# v1_0.net
KiCad netlist of a schematic drawn in Altium Designer
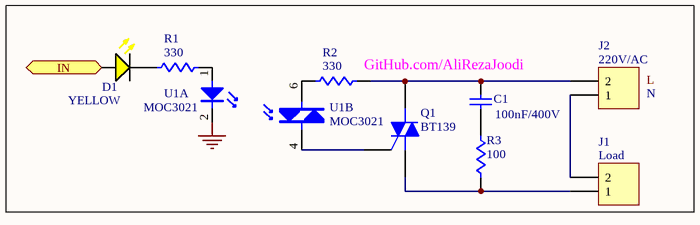
[diagram p0: v1.0.SchDoc]

(export (version "E")
  (design (tool "Eeschema 10.0.6"))
  (components
    (comp (ref "C1")
      (value "100nF/400V")
      (footprint "CAPR7.62-6.8x5")
      (description "Capacitor")
      (fields (field (name "MANUFACTURER") "Generic Components") (field (name "PUBLISHER") "Altium Limited"))
      (libsource (lib "Miscellaneous Devices") (part "Cap"))
    )
    (comp (ref "D1")
      (value "YELLOW")
      (footprint "LED_THD_5MM_YELLOW")
      (description "LED, Yellow")
      (fields (field (name "MANUFACTURER") "Generic Components") (field (name "PUBLISHER") "Altium Limited"))
      (libsource (lib "Display") (part "LED_YELLOW"))
    )
    (comp (ref "J1")
      (value "2PIN")
      (footprint "Fonics_2PIN_1")
      (description "Header, 2-Pin")
      (fields (field (name "PUBLISHER") "Altium Limited"))
      (libsource (lib "Miscellaneous Connectors") (part "Header 2"))
    )
    (comp (ref "J2")
      (value "2PIN")
      (footprint "Fonics_2PIN_1")
      (description "Header, 2-Pin")
      (fields (field (name "PUBLISHER") "Altium Limited"))
      (libsource (lib "Miscellaneous Connectors") (part "Header 2"))
    )
    (comp (ref "Q1")
      (value "BT139")
      (footprint "TO220V")
      (description "Silicon Bidirectional Triode Thyristor")
      (fields (field (name "MANUFACTURER") "Generic Components") (field (name "PUBLISHER") "Altium Limited"))
      (libsource (lib "Miscellaneous Devices") (part "Triac"))
    )
    (comp (ref "R1")
      (value "330")
      (footprint "AXIAL-0.4")
      (description "Resistor")
      (fields (field (name "MANUFACTURER") "Generic Components") (field (name "PUBLISHER") "Altium Limited"))
      (libsource (lib "Miscellaneous Devices") (part "Res1"))
    )
    (comp (ref "R2")
      (value "330")
      (footprint "AXIAL-0.4")
      (description "Resistor")
      (fields (field (name "MANUFACTURER") "Generic Components") (field (name "PUBLISHER") "Altium Limited"))
      (libsource (lib "Miscellaneous Devices") (part "Res1"))
    )
    (comp (ref "R3")
      (value "100")
      (footprint "AXIAL-0.4")
      (description "Resistor")
      (fields (field (name "MANUFACTURER") "Generic Components") (field (name "PUBLISHER") "Altium Limited"))
      (libsource (lib "Miscellaneous Devices") (part "Res1"))
    )
    (comp (ref "U1")
      (value "MOC3021")
      (footprint "DIP_6")
      (description "Opto-Triac")
      (libsource (lib "Other_Myself") (part "MOC3021"))
    )
  )
  (nets
    (net (code "1") (name "/IN") (class "Default")
      (node (ref "D1") (pin "1") (pinfunction "A_1") (pintype "passive"))
    )
    (net (code "2") (name "GND") (class "Default")
      (node (ref "U1") (pin "2") (pinfunction "K_2") (pintype "power_in"))
    )
    (net (code "3") (name "Net-(C1-Pad1)") (class "Default")
      (node (ref "C1") (pin "1") (pinfunction "1_1") (pintype "passive"))
      (node (ref "R3") (pin "2") (pinfunction "2_2") (pintype "passive"))
    )
    (net (code "4") (name "Net-(D1-K)") (class "Default")
      (node (ref "D1") (pin "2") (pinfunction "K_2") (pintype "passive"))
      (node (ref "R1") (pin "1") (pinfunction "1_1") (pintype "passive"))
    )
    (net (code "5") (name "Net-(J1-Pad2)") (class "Default")
      (node (ref "J1") (pin "2") (pinfunction "2_2") (pintype "passive"))
      (node (ref "J2") (pin "1") (pinfunction "1_1") (pintype "passive"))
    )
    (net (code "6") (name "Net-(Q1-G)") (class "Default")
      (node (ref "Q1") (pin "3") (pinfunction "G_3") (pintype "passive"))
      (node (ref "U1") (pin "4") (pinfunction "A/K_4") (pintype "passive"))
    )
    (net (code "7") (name "Net-(Q1-M1)") (class "Default")
      (node (ref "J1") (pin "1") (pinfunction "1_1") (pintype "passive"))
      (node (ref "Q1") (pin "1") (pinfunction "M1_1") (pintype "passive"))
      (node (ref "R3") (pin "1") (pinfunction "1_1") (pintype "passive"))
    )
    (net (code "8") (name "Net-(Q1-M2)") (class "Default")
      (node (ref "C1") (pin "2") (pinfunction "2_2") (pintype "passive"))
      (node (ref "J2") (pin "2") (pinfunction "2_2") (pintype "passive"))
      (node (ref "Q1") (pin "2") (pinfunction "M2_2") (pintype "passive"))
      (node (ref "R2") (pin "2") (pinfunction "2_2") (pintype "passive"))
    )
    (net (code "9") (name "Net-(R2-Pad1)") (class "Default")
      (node (ref "R2") (pin "1") (pinfunction "1_1") (pintype "passive"))
      (node (ref "U1") (pin "6") (pinfunction "A/K_6") (pintype "passive"))
    )
    (net (code "10") (name "Net-(U1A-A)") (class "Default")
      (node (ref "R1") (pin "2") (pinfunction "2_2") (pintype "passive"))
      (node (ref "U1") (pin "1") (pinfunction "A_1") (pintype "power_in"))
    )
  )
)
